# 5V0Regulator.net
KiCad netlist of a schematic drawn in Altium Designer
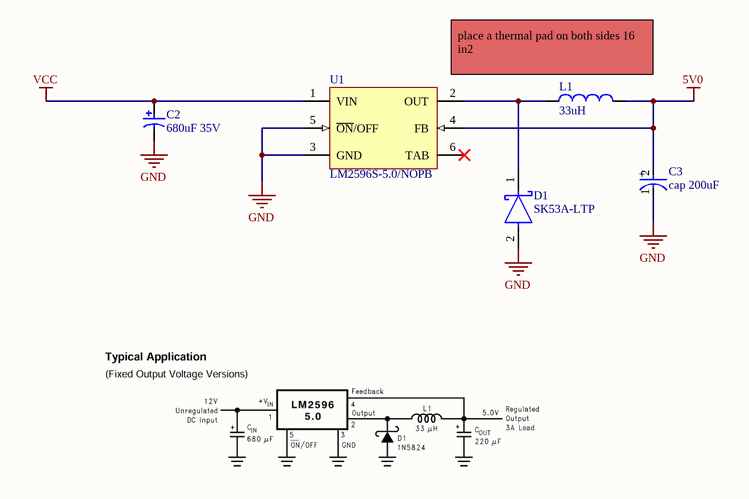
[diagram p0: 5V0Regulator.SchDoc]

(export (version "E")
  (design (tool "Eeschema 10.0.6"))
  (components
    (comp (ref "C2")
      (value "680uF 35V")
      (footprint "NIC-CAPA2-10X10_V")
      (fields (field (name "PARTNUMBER") "UUD1A681MNL1GS") (field (name "MANUFACTURER") "Nichicon"))
      (libsource (lib "Altium Content Vault") (part "NIC-CAP-P-2"))
    )
    (comp (ref "C3")
      (value "cap 200uF")
      (footprint "CAPAE7262X77M")
      (libsource (lib "Schlib1") (part "cap 200uF"))
    )
    (comp (ref "D1")
      (value "SK53A-LTP")
      (footprint "FP-DO-214AC-MFG")
      (description "DIODE SCHOTTKY 5A 30V SMA")
      (libsource (lib "Altium Content Vault") (part "1d6ec82d83fb6aee721767c19dac4b9"))
    )
    (comp (ref "L1")
      (value "33uH")
      (footprint "INDM140130X52N")
      (libsource (lib "Schlib1") (part "ind 330uH"))
    )
    (comp (ref "U1")
      (value "LM2596S-5.0/NOPB")
      (footprint "KTT0005B_M")
      (description "SIMPLE SWITCHER® Power Converter 150 KHz 3A Step-Down Voltage Regulator, 5-pin TO-263, Pb-Free")
      (fields (field (name "MANUFACTURER") "Texas Instruments"))
      (libsource (lib "Altium Content Vault") (part "PM-REG-LM2575HVS-12"))
    )
  )
  (nets
    (net (code "1") (name "5V0") (class "Default")
      (node (ref "C3") (pin "2") (pinfunction "A_2") (pintype "passive"))
      (node (ref "L1") (pin "2") (pinfunction "2_2") (pintype "passive"))
      (node (ref "U1") (pin "4") (pinfunction "FB_4") (pintype "input"))
    )
    (net (code "2") (name "GND") (class "Default")
      (node (ref "C2") (pin "2") (pinfunction "2_2") (pintype "passive"))
      (node (ref "C3") (pin "1") (pinfunction "C_1") (pintype "passive"))
      (node (ref "D1") (pin "2") (pinfunction "A_2") (pintype "passive"))
      (node (ref "U1") (pin "3") (pinfunction "GND_3") (pintype "power_in"))
      (node (ref "U1") (pin "5") (pinfunction "~{ON}/OFF_5") (pintype "input"))
    )
    (net (code "3") (name "Net-(D1-C)") (class "Default")
      (node (ref "D1") (pin "1") (pinfunction "C_1") (pintype "passive"))
      (node (ref "L1") (pin "1") (pinfunction "1_1") (pintype "passive"))
      (node (ref "U1") (pin "2") (pinfunction "OUT_2") (pintype "power_in"))
    )
    (net (code "4") (name "VCC") (class "Default")
      (node (ref "C2") (pin "1") (pinfunction "1_1") (pintype "passive"))
      (node (ref "U1") (pin "1") (pinfunction "VIN_1") (pintype "power_in"))
    )
    (net (code "5") (name "unconnected-(U1-TAB-Pad6)") (class "Default")
      (node (ref "U1") (pin "6") (pinfunction "TAB_6") (pintype "power_in+no_connect"))
    )
  )
)
